# PowerMonitor.net
KiCad netlist of a schematic drawn in EAGLE
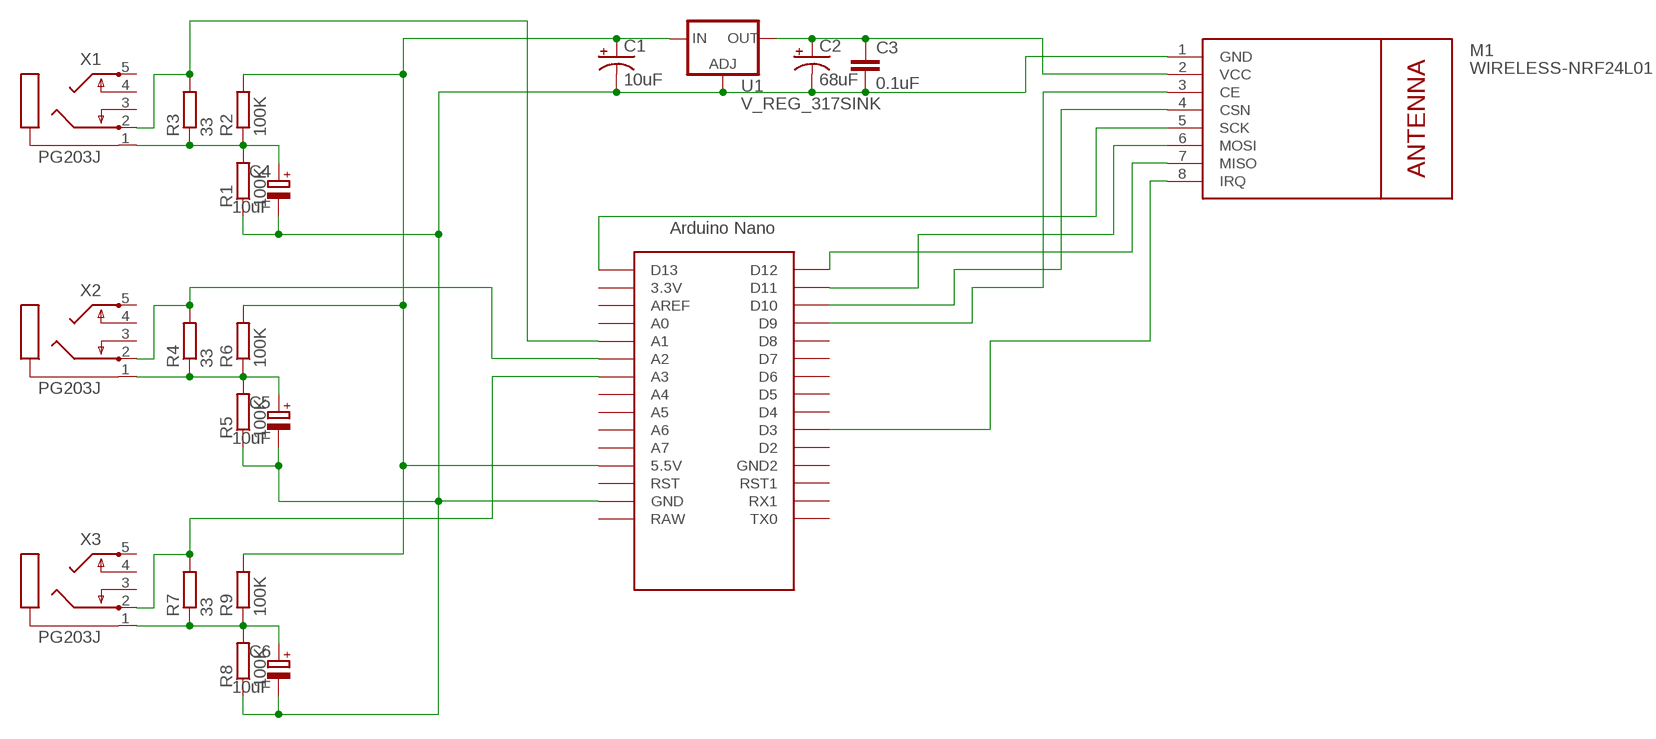
[diagram p0: schematic, sheet 1]

(export (version "E")
  (design (tool "Eeschema 10.0.6"))
  (components
    (comp (ref "C1")
      (value "10uF")
      (footprint "eagle-import:EIA3216")
      (libsource (lib "eagle-import") (part "CAP_POL1206"))
    )
    (comp (ref "C2")
      (value "68uF")
      (footprint "eagle-import:EIA3216")
      (libsource (lib "eagle-import") (part "CAP_POL1206"))
    )
    (comp (ref "C3")
      (value "0.1uF")
      (footprint "eagle-import:CAP-PTH-SMALLEZ")
      (libsource (lib "eagle-import") (part "CAPEZ"))
    )
    (comp (ref "C4")
      (value "10uF")
      (footprint "eagle-import:PANASONIC_C")
      (libsource (lib "eagle-import") (part "CPOL-EUC"))
    )
    (comp (ref "C5")
      (value "10uF")
      (footprint "eagle-import:PANASONIC_C")
      (libsource (lib "eagle-import") (part "CPOL-EUC"))
    )
    (comp (ref "C6")
      (value "10uF")
      (footprint "eagle-import:PANASONIC_C")
      (libsource (lib "eagle-import") (part "CPOL-EUC"))
    )
    (comp (ref "M1")
      (value "WIRELESS-NRF24L01")
      (footprint "eagle-import:WIRELESS-NRF24L01")
      (libsource (lib "eagle-import") (part "WIRELESS-NRF24L01"))
    )
    (comp (ref "R1")
      (value "100K")
      (footprint "eagle-import:M0805")
      (libsource (lib "eagle-import") (part "R-EU_M0805"))
    )
    (comp (ref "R2")
      (value "100K")
      (footprint "eagle-import:M0805")
      (libsource (lib "eagle-import") (part "R-EU_M0805"))
    )
    (comp (ref "R3")
      (value "33")
      (footprint "eagle-import:M0805")
      (libsource (lib "eagle-import") (part "R-EU_M0805"))
    )
    (comp (ref "R4")
      (value "33")
      (footprint "eagle-import:M0805")
      (libsource (lib "eagle-import") (part "R-EU_M0805"))
    )
    (comp (ref "R5")
      (value "100K")
      (footprint "eagle-import:M0805")
      (libsource (lib "eagle-import") (part "R-EU_M0805"))
    )
    (comp (ref "R6")
      (value "100K")
      (footprint "eagle-import:M0805")
      (libsource (lib "eagle-import") (part "R-EU_M0805"))
    )
    (comp (ref "R7")
      (value "33")
      (footprint "eagle-import:M0805")
      (libsource (lib "eagle-import") (part "R-EU_M0805"))
    )
    (comp (ref "R8")
      (value "100K")
      (footprint "eagle-import:M0805")
      (libsource (lib "eagle-import") (part "R-EU_M0805"))
    )
    (comp (ref "R9")
      (value "100K")
      (footprint "eagle-import:M0805")
      (libsource (lib "eagle-import") (part "R-EU_M0805"))
    )
    (comp (ref "U$1")
      (value "NANO")
      (footprint "eagle-import:NANO")
      (libsource (lib "eagle-import") (part "NANO"))
    )
    (comp (ref "U1")
      (value "V_REG_317SINK")
      (footprint "eagle-import:TO220-ADJ")
      (libsource (lib "eagle-import") (part "V_REG_317SINK"))
    )
    (comp (ref "X1")
      (value "PG203J")
      (footprint "eagle-import:PG203J")
      (libsource (lib "eagle-import") (part "PG203J"))
    )
    (comp (ref "X2")
      (value "PG203J")
      (footprint "eagle-import:PG203J")
      (libsource (lib "eagle-import") (part "PG203J"))
    )
    (comp (ref "X3")
      (value "PG203J")
      (footprint "eagle-import:PG203J")
      (libsource (lib "eagle-import") (part "PG203J"))
    )
  )
  (nets
    (net (code "1") (name "Net-(C1-+)") (class "Default")
      (node (ref "C1") (pin "A") (pinfunction "+_A") (pintype "passive"))
      (node (ref "R2") (pin "2") (pinfunction "2_2") (pintype "passive"))
      (node (ref "R6") (pin "2") (pinfunction "2_2") (pintype "passive"))
      (node (ref "R9") (pin "2") (pinfunction "2_2") (pintype "passive"))
      (node (ref "U$1") (pin "5V") (pinfunction "5.5V_5V") (pintype "bidirectional"))
      (node (ref "U1") (pin "IN") (pinfunction "IN_IN") (pintype "input"))
    )
    (net (code "2") (name "Net-(C1--)") (class "Default")
      (node (ref "C1") (pin "C") (pinfunction "-_C") (pintype "passive"))
      (node (ref "C2") (pin "C") (pinfunction "-_C") (pintype "passive"))
      (node (ref "C3") (pin "2") (pinfunction "2_2") (pintype "passive"))
      (node (ref "C4") (pin "-") (pinfunction "-_-") (pintype "passive"))
      (node (ref "C5") (pin "-") (pinfunction "-_-") (pintype "passive"))
      (node (ref "C6") (pin "-") (pinfunction "-_-") (pintype "passive"))
      (node (ref "M1") (pin "1") (pinfunction "GND_1") (pintype "power_in"))
      (node (ref "R1") (pin "1") (pinfunction "1_1") (pintype "passive"))
      (node (ref "R5") (pin "1") (pinfunction "1_1") (pintype "passive"))
      (node (ref "R8") (pin "1") (pinfunction "1_1") (pintype "passive"))
      (node (ref "U$1") (pin "GND") (pinfunction "GND_GND") (pintype "bidirectional"))
      (node (ref "U1") (pin "ADJ") (pinfunction "ADJ_ADJ") (pintype "input"))
    )
    (net (code "3") (name "Net-(C2-+)") (class "Default")
      (node (ref "C2") (pin "A") (pinfunction "+_A") (pintype "passive"))
      (node (ref "C3") (pin "1") (pinfunction "1_1") (pintype "passive"))
      (node (ref "M1") (pin "2") (pinfunction "VCC_2") (pintype "power_in"))
      (node (ref "U1") (pin "OUT") (pinfunction "OUT_OUT") (pintype "output"))
    )
    (net (code "4") (name "Net-(C4-Pad+)") (class "Default")
      (node (ref "C4") (pin "+") (pinfunction "+_+") (pintype "passive"))
      (node (ref "R1") (pin "2") (pinfunction "2_2") (pintype "passive"))
      (node (ref "R2") (pin "1") (pinfunction "1_1") (pintype "passive"))
      (node (ref "R3") (pin "1") (pinfunction "1_1") (pintype "passive"))
      (node (ref "X1") (pin "1") (pinfunction "1_1") (pintype "passive"))
    )
    (net (code "5") (name "Net-(C5-Pad+)") (class "Default")
      (node (ref "C5") (pin "+") (pinfunction "+_+") (pintype "passive"))
      (node (ref "R4") (pin "1") (pinfunction "1_1") (pintype "passive"))
      (node (ref "R5") (pin "2") (pinfunction "2_2") (pintype "passive"))
      (node (ref "R6") (pin "1") (pinfunction "1_1") (pintype "passive"))
      (node (ref "X2") (pin "1") (pinfunction "1_1") (pintype "passive"))
    )
    (net (code "6") (name "Net-(C6-Pad+)") (class "Default")
      (node (ref "C6") (pin "+") (pinfunction "+_+") (pintype "passive"))
      (node (ref "R7") (pin "1") (pinfunction "1_1") (pintype "passive"))
      (node (ref "R8") (pin "2") (pinfunction "2_2") (pintype "passive"))
      (node (ref "R9") (pin "1") (pinfunction "1_1") (pintype "passive"))
      (node (ref "X3") (pin "1") (pinfunction "1_1") (pintype "passive"))
    )
    (net (code "7") (name "Net-(M1-CE)") (class "Default")
      (node (ref "M1") (pin "3") (pinfunction "CE_3") (pintype "bidirectional"))
      (node (ref "U$1") (pin "D9") (pinfunction "D9_D9") (pintype "bidirectional"))
    )
    (net (code "8") (name "Net-(M1-CSN)") (class "Default")
      (node (ref "M1") (pin "4") (pinfunction "CSN_4") (pintype "bidirectional"))
      (node (ref "U$1") (pin "D10") (pinfunction "D10_D10") (pintype "bidirectional"))
    )
    (net (code "9") (name "Net-(M1-IRQ)") (class "Default")
      (node (ref "M1") (pin "8") (pinfunction "IRQ_8") (pintype "bidirectional"))
      (node (ref "U$1") (pin "D3") (pinfunction "D3_D3") (pintype "bidirectional"))
    )
    (net (code "10") (name "Net-(M1-MISO)") (class "Default")
      (node (ref "M1") (pin "7") (pinfunction "MISO_7") (pintype "bidirectional"))
      (node (ref "U$1") (pin "D12") (pinfunction "D12_D12") (pintype "bidirectional"))
    )
    (net (code "11") (name "Net-(M1-MOSI)") (class "Default")
      (node (ref "M1") (pin "6") (pinfunction "MOSI_6") (pintype "bidirectional"))
      (node (ref "U$1") (pin "D11") (pinfunction "D11_D11") (pintype "bidirectional"))
    )
    (net (code "12") (name "Net-(M1-SCK)") (class "Default")
      (node (ref "M1") (pin "5") (pinfunction "SCK_5") (pintype "bidirectional"))
      (node (ref "U$1") (pin "D13") (pinfunction "D13_D13") (pintype "bidirectional"))
    )
    (net (code "13") (name "Net-(R3-Pad2)") (class "Default")
      (node (ref "R3") (pin "2") (pinfunction "2_2") (pintype "passive"))
      (node (ref "U$1") (pin "A1") (pinfunction "A1_A1") (pintype "bidirectional"))
      (node (ref "X1") (pin "2") (pinfunction "2_2") (pintype "passive"))
    )
    (net (code "14") (name "Net-(R4-Pad2)") (class "Default")
      (node (ref "R4") (pin "2") (pinfunction "2_2") (pintype "passive"))
      (node (ref "U$1") (pin "A2") (pinfunction "A2_A2") (pintype "bidirectional"))
      (node (ref "X2") (pin "2") (pinfunction "2_2") (pintype "passive"))
    )
    (net (code "15") (name "Net-(R7-Pad2)") (class "Default")
      (node (ref "R7") (pin "2") (pinfunction "2_2") (pintype "passive"))
      (node (ref "U$1") (pin "A3") (pinfunction "A3_A3") (pintype "bidirectional"))
      (node (ref "X3") (pin "2") (pinfunction "2_2") (pintype "passive"))
    )
    (net (code "16") (name "unconnected-(U$1-GND2-PadGND1)") (class "Default")
      (node (ref "U$1") (pin "GND1") (pinfunction "GND2_GND1") (pintype "bidirectional"))
    )
    (net (code "17") (name "unconnected-(U$1-Pad3.3V)") (class "Default")
      (node (ref "U$1") (pin "3.3V") (pinfunction "3.3V_3.3V") (pintype "bidirectional"))
    )
    (net (code "18") (name "unconnected-(U$1-PadA0)") (class "Default")
      (node (ref "U$1") (pin "A0") (pinfunction "A0_A0") (pintype "bidirectional"))
    )
    (net (code "19") (name "unconnected-(U$1-PadA4)") (class "Default")
      (node (ref "U$1") (pin "A4") (pinfunction "A4_A4") (pintype "bidirectional"))
    )
    (net (code "20") (name "unconnected-(U$1-PadA5)") (class "Default")
      (node (ref "U$1") (pin "A5") (pinfunction "A5_A5") (pintype "bidirectional"))
    )
    (net (code "21") (name "unconnected-(U$1-PadA6)") (class "Default")
      (node (ref "U$1") (pin "A6") (pinfunction "A6_A6") (pintype "bidirectional"))
    )
    (net (code "22") (name "unconnected-(U$1-PadA7)") (class "Default")
      (node (ref "U$1") (pin "A7") (pinfunction "A7_A7") (pintype "bidirectional"))
    )
    (net (code "23") (name "unconnected-(U$1-PadAREF)") (class "Default")
      (node (ref "U$1") (pin "AREF") (pinfunction "AREF_AREF") (pintype "bidirectional"))
    )
    (net (code "24") (name "unconnected-(U$1-PadD2)") (class "Default")
      (node (ref "U$1") (pin "D2") (pinfunction "D2_D2") (pintype "bidirectional"))
    )
    (net (code "25") (name "unconnected-(U$1-PadD4)") (class "Default")
      (node (ref "U$1") (pin "D4") (pinfunction "D4_D4") (pintype "bidirectional"))
    )
    (net (code "26") (name "unconnected-(U$1-PadD5)") (class "Default")
      (node (ref "U$1") (pin "D5") (pinfunction "D5_D5") (pintype "bidirectional"))
    )
    (net (code "27") (name "unconnected-(U$1-PadD6)") (class "Default")
      (node (ref "U$1") (pin "D6") (pinfunction "D6_D6") (pintype "bidirectional"))
    )
    (net (code "28") (name "unconnected-(U$1-PadD7)") (class "Default")
      (node (ref "U$1") (pin "D7") (pinfunction "D7_D7") (pintype "bidirectional"))
    )
    (net (code "29") (name "unconnected-(U$1-PadD8)") (class "Default")
      (node (ref "U$1") (pin "D8") (pinfunction "D8_D8") (pintype "bidirectional"))
    )
    (net (code "30") (name "unconnected-(U$1-PadICSP1)") (class "Default")
      (node (ref "U$1") (pin "ICSP1") (pinfunction "ICSP1_ICSP1") (pintype "bidirectional"))
    )
    (net (code "31") (name "unconnected-(U$1-PadICSP2)") (class "Default")
      (node (ref "U$1") (pin "ICSP2") (pinfunction "ICSP2_ICSP2") (pintype "bidirectional"))
    )
    (net (code "32") (name "unconnected-(U$1-PadICSP3)") (class "Default")
      (node (ref "U$1") (pin "ICSP3") (pinfunction "ICSP3_ICSP3") (pintype "bidirectional"))
    )
    (net (code "33") (name "unconnected-(U$1-PadICSP4)") (class "Default")
      (node (ref "U$1") (pin "ICSP4") (pinfunction "ICSP4_ICSP4") (pintype "bidirectional"))
    )
    (net (code "34") (name "unconnected-(U$1-PadICSP5)") (class "Default")
      (node (ref "U$1") (pin "ICSP5") (pinfunction "ICSP5_ICSP5") (pintype "bidirectional"))
    )
    (net (code "35") (name "unconnected-(U$1-PadICSP6)") (class "Default")
      (node (ref "U$1") (pin "ICSP6") (pinfunction "ICSP6_ICSP6") (pintype "bidirectional"))
    )
    (net (code "36") (name "unconnected-(U$1-PadRAW)") (class "Default")
      (node (ref "U$1") (pin "RAW") (pinfunction "RAW_RAW") (pintype "bidirectional"))
    )
    (net (code "37") (name "unconnected-(U$1-PadRST)") (class "Default")
      (node (ref "U$1") (pin "RST") (pinfunction "RST_RST") (pintype "bidirectional"))
    )
    (net (code "38") (name "unconnected-(U$1-PadRST1)") (class "Default")
      (node (ref "U$1") (pin "RST1") (pinfunction "RST1_RST1") (pintype "bidirectional"))
    )
    (net (code "39") (name "unconnected-(U$1-PadRX1)") (class "Default")
      (node (ref "U$1") (pin "RX1") (pinfunction "RX1_RX1") (pintype "bidirectional"))
    )
    (net (code "40") (name "unconnected-(U$1-PadTX0)") (class "Default")
      (node (ref "U$1") (pin "TX0") (pinfunction "TX0_TX0") (pintype "bidirectional"))
    )
    (net (code "41") (name "unconnected-(X1-Pad3)") (class "Default")
      (node (ref "X1") (pin "3") (pinfunction "3_3") (pintype "passive"))
    )
    (net (code "42") (name "unconnected-(X1-Pad4)") (class "Default")
      (node (ref "X1") (pin "4") (pinfunction "4_4") (pintype "passive"))
    )
    (net (code "43") (name "unconnected-(X1-Pad5)") (class "Default")
      (node (ref "X1") (pin "5") (pinfunction "5_5") (pintype "passive"))
    )
    (net (code "44") (name "unconnected-(X2-Pad3)") (class "Default")
      (node (ref "X2") (pin "3") (pinfunction "3_3") (pintype "passive"))
    )
    (net (code "45") (name "unconnected-(X2-Pad4)") (class "Default")
      (node (ref "X2") (pin "4") (pinfunction "4_4") (pintype "passive"))
    )
    (net (code "46") (name "unconnected-(X2-Pad5)") (class "Default")
      (node (ref "X2") (pin "5") (pinfunction "5_5") (pintype "passive"))
    )
    (net (code "47") (name "unconnected-(X3-Pad3)") (class "Default")
      (node (ref "X3") (pin "3") (pinfunction "3_3") (pintype "passive"))
    )
    (net (code "48") (name "unconnected-(X3-Pad4)") (class "Default")
      (node (ref "X3") (pin "4") (pinfunction "4_4") (pintype "passive"))
    )
    (net (code "49") (name "unconnected-(X3-Pad5)") (class "Default")
      (node (ref "X3") (pin "5") (pinfunction "5_5") (pintype "passive"))
    )
  )
)
